# OUTPUTs.net
KiCad netlist of a schematic drawn in Altium Designer
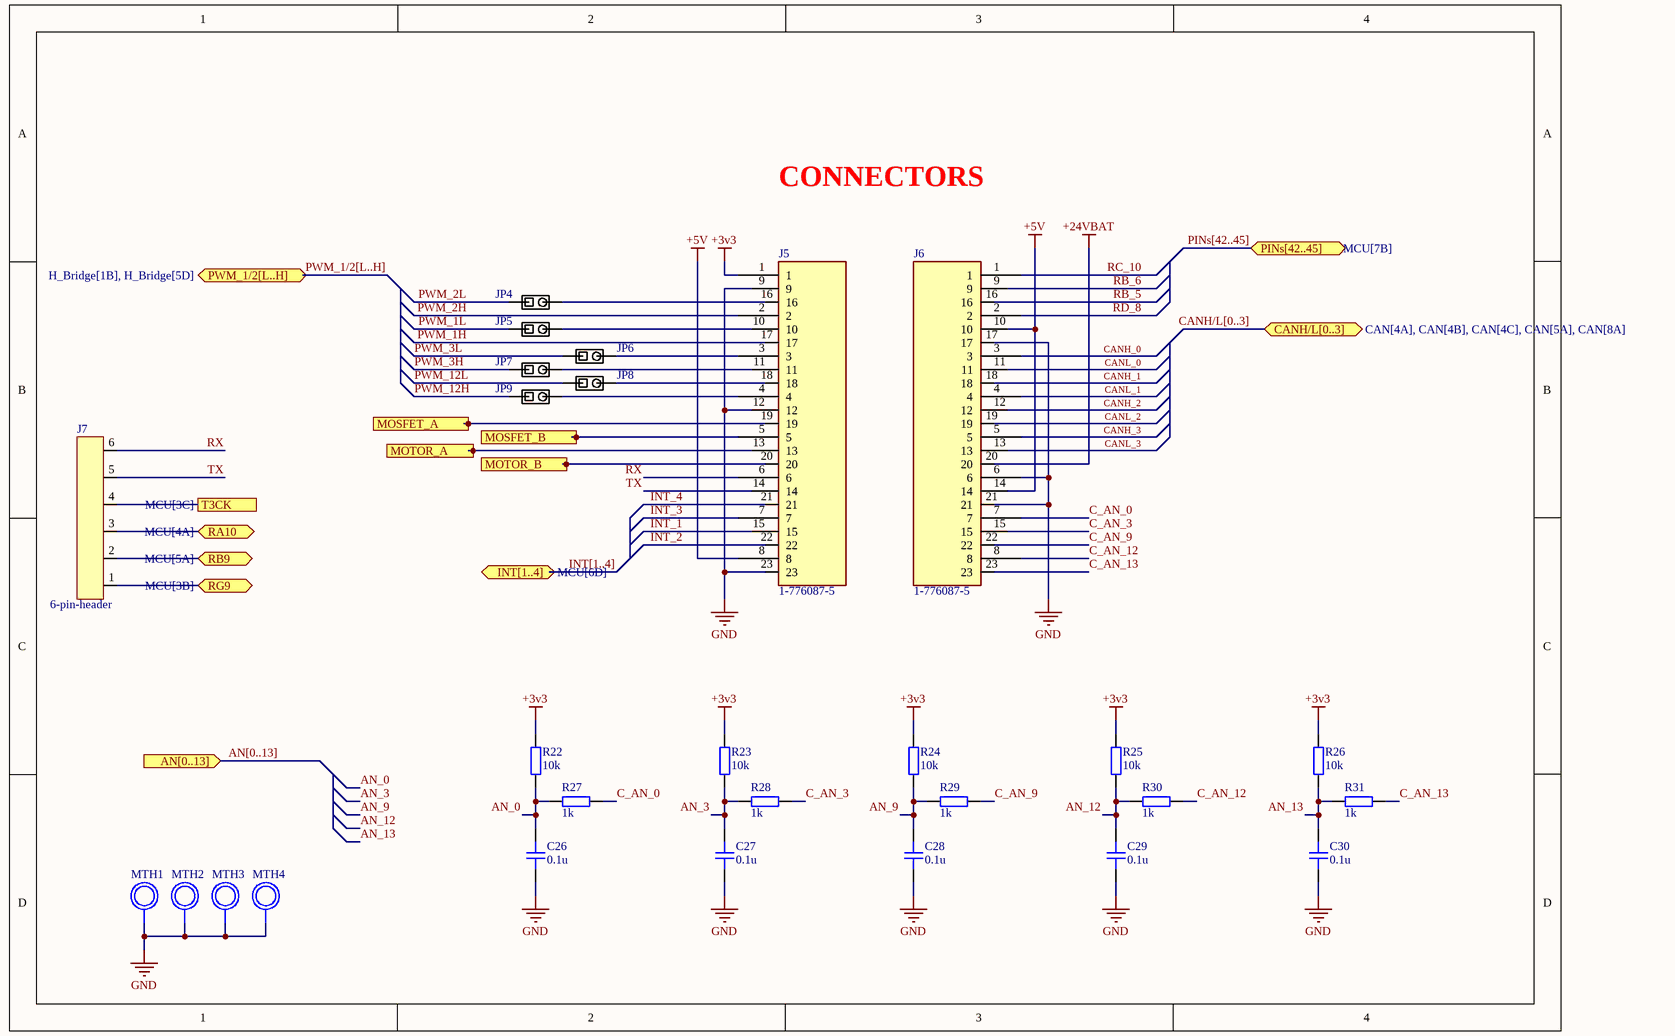
[diagram p0: OUTPUTs.SchDoc]

(export (version "E")
  (design (tool "Eeschema 10.0.6"))
  (components
    (comp (ref "C26")
      (value "0.1u")
      (footprint "CAP_0805")
      (description "Capacitor SMD 0805 16V")
      (libsource (lib "Pedro_Integrated_Library") (part "CAP_0805_16V"))
    )
    (comp (ref "C27")
      (value "0.1u")
      (footprint "CAP_0805")
      (description "Capacitor SMD 0805 16V")
      (libsource (lib "Pedro_Integrated_Library") (part "CAP_0805_16V"))
    )
    (comp (ref "C28")
      (value "0.1u")
      (footprint "CAP_0805")
      (description "Capacitor SMD 0805 16V")
      (libsource (lib "Pedro_Integrated_Library") (part "CAP_0805_16V"))
    )
    (comp (ref "C29")
      (value "0.1u")
      (footprint "CAP_0805")
      (description "Capacitor SMD 0805 16V")
      (libsource (lib "Pedro_Integrated_Library") (part "CAP_0805_16V"))
    )
    (comp (ref "C30")
      (value "0.1u")
      (footprint "CAP_0805")
      (description "Capacitor SMD 0805 16V")
      (libsource (lib "Pedro_Integrated_Library") (part "CAP_0805_16V"))
    )
    (comp (ref "J5")
      (value "1-776087-5")
      (footprint "TE_1-776087-5")
      (description "CONN HDR 23POS R/A W/GASKET AU")
      (fields (field (name "MF") "{'manufacturer': 'TE Connectivity'}"))
      (libsource (lib "1-776087-5") (part "1-776087-5"))
    )
    (comp (ref "J6")
      (value "1-776087-5")
      (footprint "TE_1-776087-5")
      (description "CONN HDR 23POS R/A W/GASKET AU")
      (fields (field (name "MF") "{'manufacturer': 'TE Connectivity'}"))
      (libsource (lib "") (part "1-776087-5_1"))
    )
    (comp (ref "J7")
      (value "6-pin-header")
      (footprint "G800W302018EU")
      (description "Pin Header 6 Position 2.54mm Pitch")
      (fields
        (field (name "MANUFACTURER") "Amphenol")
        (field (name "MANUFACTURER PART NUMBER") "G800W302018EU")
      )
      (libsource (lib "PhilsLab") (part "G800W302018EU"))
    )
    (comp (ref "JP4")
      (value "Solder Jumper")
      (footprint "SolderJumper_Single")
      (description "Solder Jumper Single 0.5mm Pitch")
      (libsource (lib "Pedro_Integrated_Library") (part "SolderJumper_Single"))
    )
    (comp (ref "JP5")
      (value "Solder Jumper")
      (footprint "SolderJumper_Single")
      (description "Solder Jumper Single 0.5mm Pitch")
      (libsource (lib "Pedro_Integrated_Library") (part "SolderJumper_Single"))
    )
    (comp (ref "JP6")
      (value "Solder Jumper")
      (footprint "SolderJumper_Single")
      (description "Solder Jumper Single 0.5mm Pitch")
      (libsource (lib "Pedro_Integrated_Library") (part "SolderJumper_Single"))
    )
    (comp (ref "JP7")
      (value "Solder Jumper")
      (footprint "SolderJumper_Single")
      (description "Solder Jumper Single 0.5mm Pitch")
      (libsource (lib "Pedro_Integrated_Library") (part "SolderJumper_Single"))
    )
    (comp (ref "JP8")
      (value "Solder Jumper")
      (footprint "SolderJumper_Single")
      (description "Solder Jumper Single 0.5mm Pitch")
      (libsource (lib "Pedro_Integrated_Library") (part "SolderJumper_Single"))
    )
    (comp (ref "JP9")
      (value "Solder Jumper")
      (footprint "SolderJumper_Single")
      (description "Solder Jumper Single 0.5mm Pitch")
      (libsource (lib "Pedro_Integrated_Library") (part "SolderJumper_Single"))
    )
    (comp (ref "MTH1")
      (value "Mounting_Hole_3.5mm")
      (footprint "Mounting_Hole_3.5mm")
      (libsource (lib "Pedro_Integrated_Library") (part "Mounting_Hole_3.5mm"))
    )
    (comp (ref "MTH2")
      (value "Mounting_Hole_3.5mm")
      (footprint "Mounting_Hole_3.5mm")
      (libsource (lib "Pedro_Integrated_Library") (part "Mounting_Hole_3.5mm"))
    )
    (comp (ref "MTH3")
      (value "Mounting_Hole_3.5mm")
      (footprint "Mounting_Hole_3.5mm")
      (libsource (lib "Pedro_Integrated_Library") (part "Mounting_Hole_3.5mm"))
    )
    (comp (ref "MTH4")
      (value "Mounting_Hole_3.5mm")
      (footprint "Mounting_Hole_3.5mm")
      (libsource (lib "Pedro_Integrated_Library") (part "Mounting_Hole_3.5mm"))
    )
    (comp (ref "R22")
      (value "10k")
      (footprint "RES_0805")
      (description "Resistor SMD 0805")
      (libsource (lib "Pedro_Integrated_Library") (part "RES_0805"))
    )
    (comp (ref "R23")
      (value "10k")
      (footprint "RES_0805")
      (description "Resistor SMD 0805")
      (libsource (lib "Pedro_Integrated_Library") (part "RES_0805"))
    )
    (comp (ref "R24")
      (value "10k")
      (footprint "RES_0805")
      (description "Resistor SMD 0805")
      (libsource (lib "Pedro_Integrated_Library") (part "RES_0805"))
    )
    (comp (ref "R25")
      (value "10k")
      (footprint "RES_0805")
      (description "Resistor SMD 0805")
      (libsource (lib "Pedro_Integrated_Library") (part "RES_0805"))
    )
    (comp (ref "R26")
      (value "10k")
      (footprint "RES_0805")
      (description "Resistor SMD 0805")
      (libsource (lib "Pedro_Integrated_Library") (part "RES_0805"))
    )
    (comp (ref "R27")
      (value "1k")
      (footprint "RES_0805")
      (description "Resistor SMD 0805")
      (libsource (lib "Pedro_Integrated_Library") (part "RES_0805"))
    )
    (comp (ref "R28")
      (value "1k")
      (footprint "RES_0805")
      (description "Resistor SMD 0805")
      (libsource (lib "Pedro_Integrated_Library") (part "RES_0805"))
    )
    (comp (ref "R29")
      (value "1k")
      (footprint "RES_0805")
      (description "Resistor SMD 0805")
      (libsource (lib "Pedro_Integrated_Library") (part "RES_0805"))
    )
    (comp (ref "R30")
      (value "1k")
      (footprint "RES_0805")
      (description "Resistor SMD 0805")
      (libsource (lib "Pedro_Integrated_Library") (part "RES_0805"))
    )
    (comp (ref "R31")
      (value "1k")
      (footprint "RES_0805")
      (description "Resistor SMD 0805")
      (libsource (lib "Pedro_Integrated_Library") (part "RES_0805"))
    )
  )
  (nets
    (net (code "28") (name "+3v3") (class "Default")
      (node (ref "J5") (pin "1") (pinfunction "1_1") (pintype "passive"))
      (node (ref "R22") (pin "2") (pinfunction "2_2") (pintype "passive"))
      (node (ref "R23") (pin "2") (pinfunction "2_2") (pintype "passive"))
      (node (ref "R24") (pin "2") (pinfunction "2_2") (pintype "passive"))
      (node (ref "R25") (pin "2") (pinfunction "2_2") (pintype "passive"))
      (node (ref "R26") (pin "2") (pinfunction "2_2") (pintype "passive"))
    )
    (net (code "29") (name "+5V") (class "Default")
      (node (ref "J5") (pin "8") (pinfunction "8_8") (pintype "passive"))
      (node (ref "J6") (pin "10") (pinfunction "10_10") (pintype "passive"))
      (node (ref "J6") (pin "14") (pinfunction "14_14") (pintype "passive"))
    )
    (net (code "30") (name "+24VBAT") (class "Default")
      (node (ref "J6") (pin "20") (pinfunction "20_20") (pintype "passive"))
    )
    (net (code "32") (name "/AN_0") (class "Default")
      (node (ref "C26") (pin "2") (pinfunction "2_2") (pintype "passive"))
      (node (ref "R22") (pin "1") (pinfunction "1_1") (pintype "passive"))
      (node (ref "R27") (pin "1") (pinfunction "1_1") (pintype "passive"))
    )
    (net (code "33") (name "/AN_3") (class "Default")
      (node (ref "C27") (pin "2") (pinfunction "2_2") (pintype "passive"))
      (node (ref "R23") (pin "1") (pinfunction "1_1") (pintype "passive"))
      (node (ref "R28") (pin "1") (pinfunction "1_1") (pintype "passive"))
    )
    (net (code "34") (name "/AN_9") (class "Default")
      (node (ref "C28") (pin "2") (pinfunction "2_2") (pintype "passive"))
      (node (ref "R24") (pin "1") (pinfunction "1_1") (pintype "passive"))
      (node (ref "R29") (pin "1") (pinfunction "1_1") (pintype "passive"))
    )
    (net (code "35") (name "/AN_12") (class "Default")
      (node (ref "C29") (pin "2") (pinfunction "2_2") (pintype "passive"))
      (node (ref "R25") (pin "1") (pinfunction "1_1") (pintype "passive"))
      (node (ref "R30") (pin "1") (pinfunction "1_1") (pintype "passive"))
    )
    (net (code "36") (name "/AN_13") (class "Default")
      (node (ref "C30") (pin "2") (pinfunction "2_2") (pintype "passive"))
      (node (ref "R26") (pin "1") (pinfunction "1_1") (pintype "passive"))
      (node (ref "R31") (pin "1") (pinfunction "1_1") (pintype "passive"))
    )
    (net (code "37") (name "/CANH_0") (class "Default")
      (node (ref "J6") (pin "3") (pinfunction "3_3") (pintype "passive"))
    )
    (net (code "38") (name "/CANH_1") (class "Default")
      (node (ref "J6") (pin "18") (pinfunction "18_18") (pintype "passive"))
    )
    (net (code "39") (name "/CANH_2") (class "Default")
      (node (ref "J6") (pin "12") (pinfunction "12_12") (pintype "passive"))
    )
    (net (code "40") (name "/CANH_3") (class "Default")
      (node (ref "J6") (pin "5") (pinfunction "5_5") (pintype "passive"))
    )
    (net (code "42") (name "/CANL_0") (class "Default")
      (node (ref "J6") (pin "11") (pinfunction "11_11") (pintype "passive"))
    )
    (net (code "43") (name "/CANL_1") (class "Default")
      (node (ref "J6") (pin "4") (pinfunction "4_4") (pintype "passive"))
    )
    (net (code "44") (name "/CANL_2") (class "Default")
      (node (ref "J6") (pin "19") (pinfunction "19_19") (pintype "passive"))
    )
    (net (code "45") (name "/CANL_3") (class "Default")
      (node (ref "J6") (pin "13") (pinfunction "13_13") (pintype "passive"))
    )
    (net (code "46") (name "/C_AN_0") (class "Default")
      (node (ref "J6") (pin "7") (pinfunction "7_7") (pintype "passive"))
      (node (ref "R27") (pin "2") (pinfunction "2_2") (pintype "passive"))
    )
    (net (code "47") (name "/C_AN_3") (class "Default")
      (node (ref "J6") (pin "15") (pinfunction "15_15") (pintype "passive"))
      (node (ref "R28") (pin "2") (pinfunction "2_2") (pintype "passive"))
    )
    (net (code "48") (name "/C_AN_9") (class "Default")
      (node (ref "J6") (pin "22") (pinfunction "22_22") (pintype "passive"))
      (node (ref "R29") (pin "2") (pinfunction "2_2") (pintype "passive"))
    )
    (net (code "49") (name "/C_AN_12") (class "Default")
      (node (ref "J6") (pin "8") (pinfunction "8_8") (pintype "passive"))
      (node (ref "R30") (pin "2") (pinfunction "2_2") (pintype "passive"))
    )
    (net (code "50") (name "/C_AN_13") (class "Default")
      (node (ref "J6") (pin "23") (pinfunction "23_23") (pintype "passive"))
      (node (ref "R31") (pin "2") (pinfunction "2_2") (pintype "passive"))
    )
    (net (code "52") (name "/INT_1") (class "Default")
      (node (ref "J5") (pin "15") (pinfunction "15_15") (pintype "passive"))
    )
    (net (code "53") (name "/INT_2") (class "Default")
      (node (ref "J5") (pin "22") (pinfunction "22_22") (pintype "passive"))
    )
    (net (code "54") (name "/INT_3") (class "Default")
      (node (ref "J5") (pin "7") (pinfunction "7_7") (pintype "passive"))
    )
    (net (code "55") (name "/INT_4") (class "Default")
      (node (ref "J5") (pin "21") (pinfunction "21_21") (pintype "passive"))
    )
    (net (code "56") (name "/MOSFET_A") (class "Default")
      (node (ref "J5") (pin "19") (pinfunction "19_19") (pintype "passive"))
    )
    (net (code "57") (name "/MOSFET_B") (class "Default")
      (node (ref "J5") (pin "5") (pinfunction "5_5") (pintype "passive"))
    )
    (net (code "58") (name "/MOTOR_A") (class "Default")
      (node (ref "J5") (pin "13") (pinfunction "13_13") (pintype "passive"))
    )
    (net (code "59") (name "/MOTOR_B") (class "Default")
      (node (ref "J5") (pin "20") (pinfunction "20_20") (pintype "passive"))
    )
    (net (code "61") (name "/PWM_1H") (class "Default")
      (node (ref "J5") (pin "17") (pinfunction "17_17") (pintype "passive"))
    )
    (net (code "62") (name "/PWM_1L") (class "Default")
      (node (ref "JP5") (pin "1") (pinfunction "1_1") (pintype "passive"))
    )
    (net (code "63") (name "/PWM_2H") (class "Default")
      (node (ref "J5") (pin "2") (pinfunction "2_2") (pintype "passive"))
    )
    (net (code "64") (name "/PWM_2L") (class "Default")
      (node (ref "JP4") (pin "1") (pinfunction "1_1") (pintype "passive"))
    )
    (net (code "65") (name "/PWM_3H") (class "Default")
      (node (ref "JP7") (pin "1") (pinfunction "1_1") (pintype "passive"))
    )
    (net (code "66") (name "/PWM_3L") (class "Default")
      (node (ref "JP6") (pin "1") (pinfunction "1_1") (pintype "passive"))
    )
    (net (code "67") (name "/PWM_12H") (class "Default")
      (node (ref "JP9") (pin "1") (pinfunction "1_1") (pintype "passive"))
    )
    (net (code "68") (name "/PWM_12L") (class "Default")
      (node (ref "JP8") (pin "1") (pinfunction "1_1") (pintype "passive"))
    )
    (net (code "69") (name "/RA10") (class "Default")
      (node (ref "J7") (pin "3") (pinfunction "3_3") (pintype "passive"))
    )
    (net (code "70") (name "/RB9") (class "Default")
      (node (ref "J7") (pin "2") (pinfunction "2_2") (pintype "passive"))
    )
    (net (code "71") (name "/RB_5") (class "Default")
      (node (ref "J6") (pin "16") (pinfunction "16_16") (pintype "passive"))
    )
    (net (code "72") (name "/RB_6") (class "Default")
      (node (ref "J6") (pin "9") (pinfunction "9_9") (pintype "passive"))
    )
    (net (code "73") (name "/RC_10") (class "Default")
      (node (ref "J6") (pin "1") (pinfunction "1_1") (pintype "passive"))
    )
    (net (code "74") (name "/RD_8") (class "Default")
      (node (ref "J6") (pin "2") (pinfunction "2_2") (pintype "passive"))
    )
    (net (code "75") (name "/RG9") (class "Default")
      (node (ref "J7") (pin "1") (pinfunction "1_1") (pintype "passive"))
    )
    (net (code "76") (name "/RX") (class "Default")
      (node (ref "J5") (pin "6") (pinfunction "6_6") (pintype "passive"))
      (node (ref "J7") (pin "6") (pinfunction "6_6") (pintype "passive"))
    )
    (net (code "77") (name "/T3CK") (class "Default")
      (node (ref "J7") (pin "4") (pinfunction "4_4") (pintype "passive"))
    )
    (net (code "78") (name "/TX") (class "Default")
      (node (ref "J5") (pin "14") (pinfunction "14_14") (pintype "passive"))
      (node (ref "J7") (pin "5") (pinfunction "5_5") (pintype "passive"))
    )
    (net (code "80") (name "GND") (class "Default")
      (node (ref "C26") (pin "1") (pinfunction "1_1") (pintype "passive"))
      (node (ref "C27") (pin "1") (pinfunction "1_1") (pintype "passive"))
      (node (ref "C28") (pin "1") (pinfunction "1_1") (pintype "passive"))
      (node (ref "C29") (pin "1") (pinfunction "1_1") (pintype "passive"))
      (node (ref "C30") (pin "1") (pinfunction "1_1") (pintype "passive"))
      (node (ref "J5") (pin "12") (pinfunction "12_12") (pintype "passive"))
      (node (ref "J5") (pin "23") (pinfunction "23_23") (pintype "passive"))
      (node (ref "J5") (pin "9") (pinfunction "9_9") (pintype "passive"))
      (node (ref "J6") (pin "17") (pinfunction "17_17") (pintype "passive"))
      (node (ref "J6") (pin "21") (pinfunction "21_21") (pintype "passive"))
      (node (ref "J6") (pin "6") (pinfunction "6_6") (pintype "passive"))
      (node (ref "MTH1") (pin "1") (pinfunction "1_1") (pintype "passive"))
      (node (ref "MTH2") (pin "1") (pinfunction "1_1") (pintype "passive"))
      (node (ref "MTH3") (pin "1") (pinfunction "1_1") (pintype "passive"))
      (node (ref "MTH4") (pin "1") (pinfunction "1_1") (pintype "passive"))
    )
    (net (code "81") (name "Net-(J5-Pad3)") (class "Default")
      (node (ref "J5") (pin "3") (pinfunction "3_3") (pintype "passive"))
      (node (ref "JP6") (pin "2") (pinfunction "2_2") (pintype "passive"))
    )
    (net (code "82") (name "Net-(J5-Pad4)") (class "Default")
      (node (ref "J5") (pin "4") (pinfunction "4_4") (pintype "passive"))
      (node (ref "JP9") (pin "2") (pinfunction "2_2") (pintype "passive"))
    )
    (net (code "83") (name "Net-(J5-Pad10)") (class "Default")
      (node (ref "J5") (pin "10") (pinfunction "10_10") (pintype "passive"))
      (node (ref "JP5") (pin "2") (pinfunction "2_2") (pintype "passive"))
    )
    (net (code "84") (name "Net-(J5-Pad11)") (class "Default")
      (node (ref "J5") (pin "11") (pinfunction "11_11") (pintype "passive"))
      (node (ref "JP7") (pin "2") (pinfunction "2_2") (pintype "passive"))
    )
    (net (code "85") (name "Net-(J5-Pad16)") (class "Default")
      (node (ref "J5") (pin "16") (pinfunction "16_16") (pintype "passive"))
      (node (ref "JP4") (pin "2") (pinfunction "2_2") (pintype "passive"))
    )
    (net (code "86") (name "Net-(J5-Pad18)") (class "Default")
      (node (ref "J5") (pin "18") (pinfunction "18_18") (pintype "passive"))
      (node (ref "JP8") (pin "2") (pinfunction "2_2") (pintype "passive"))
    )
  )
)
